# SCH_DS3231SupercapModule_2025-05-23.net
KiCad netlist of a schematic drawn in EasyEDA
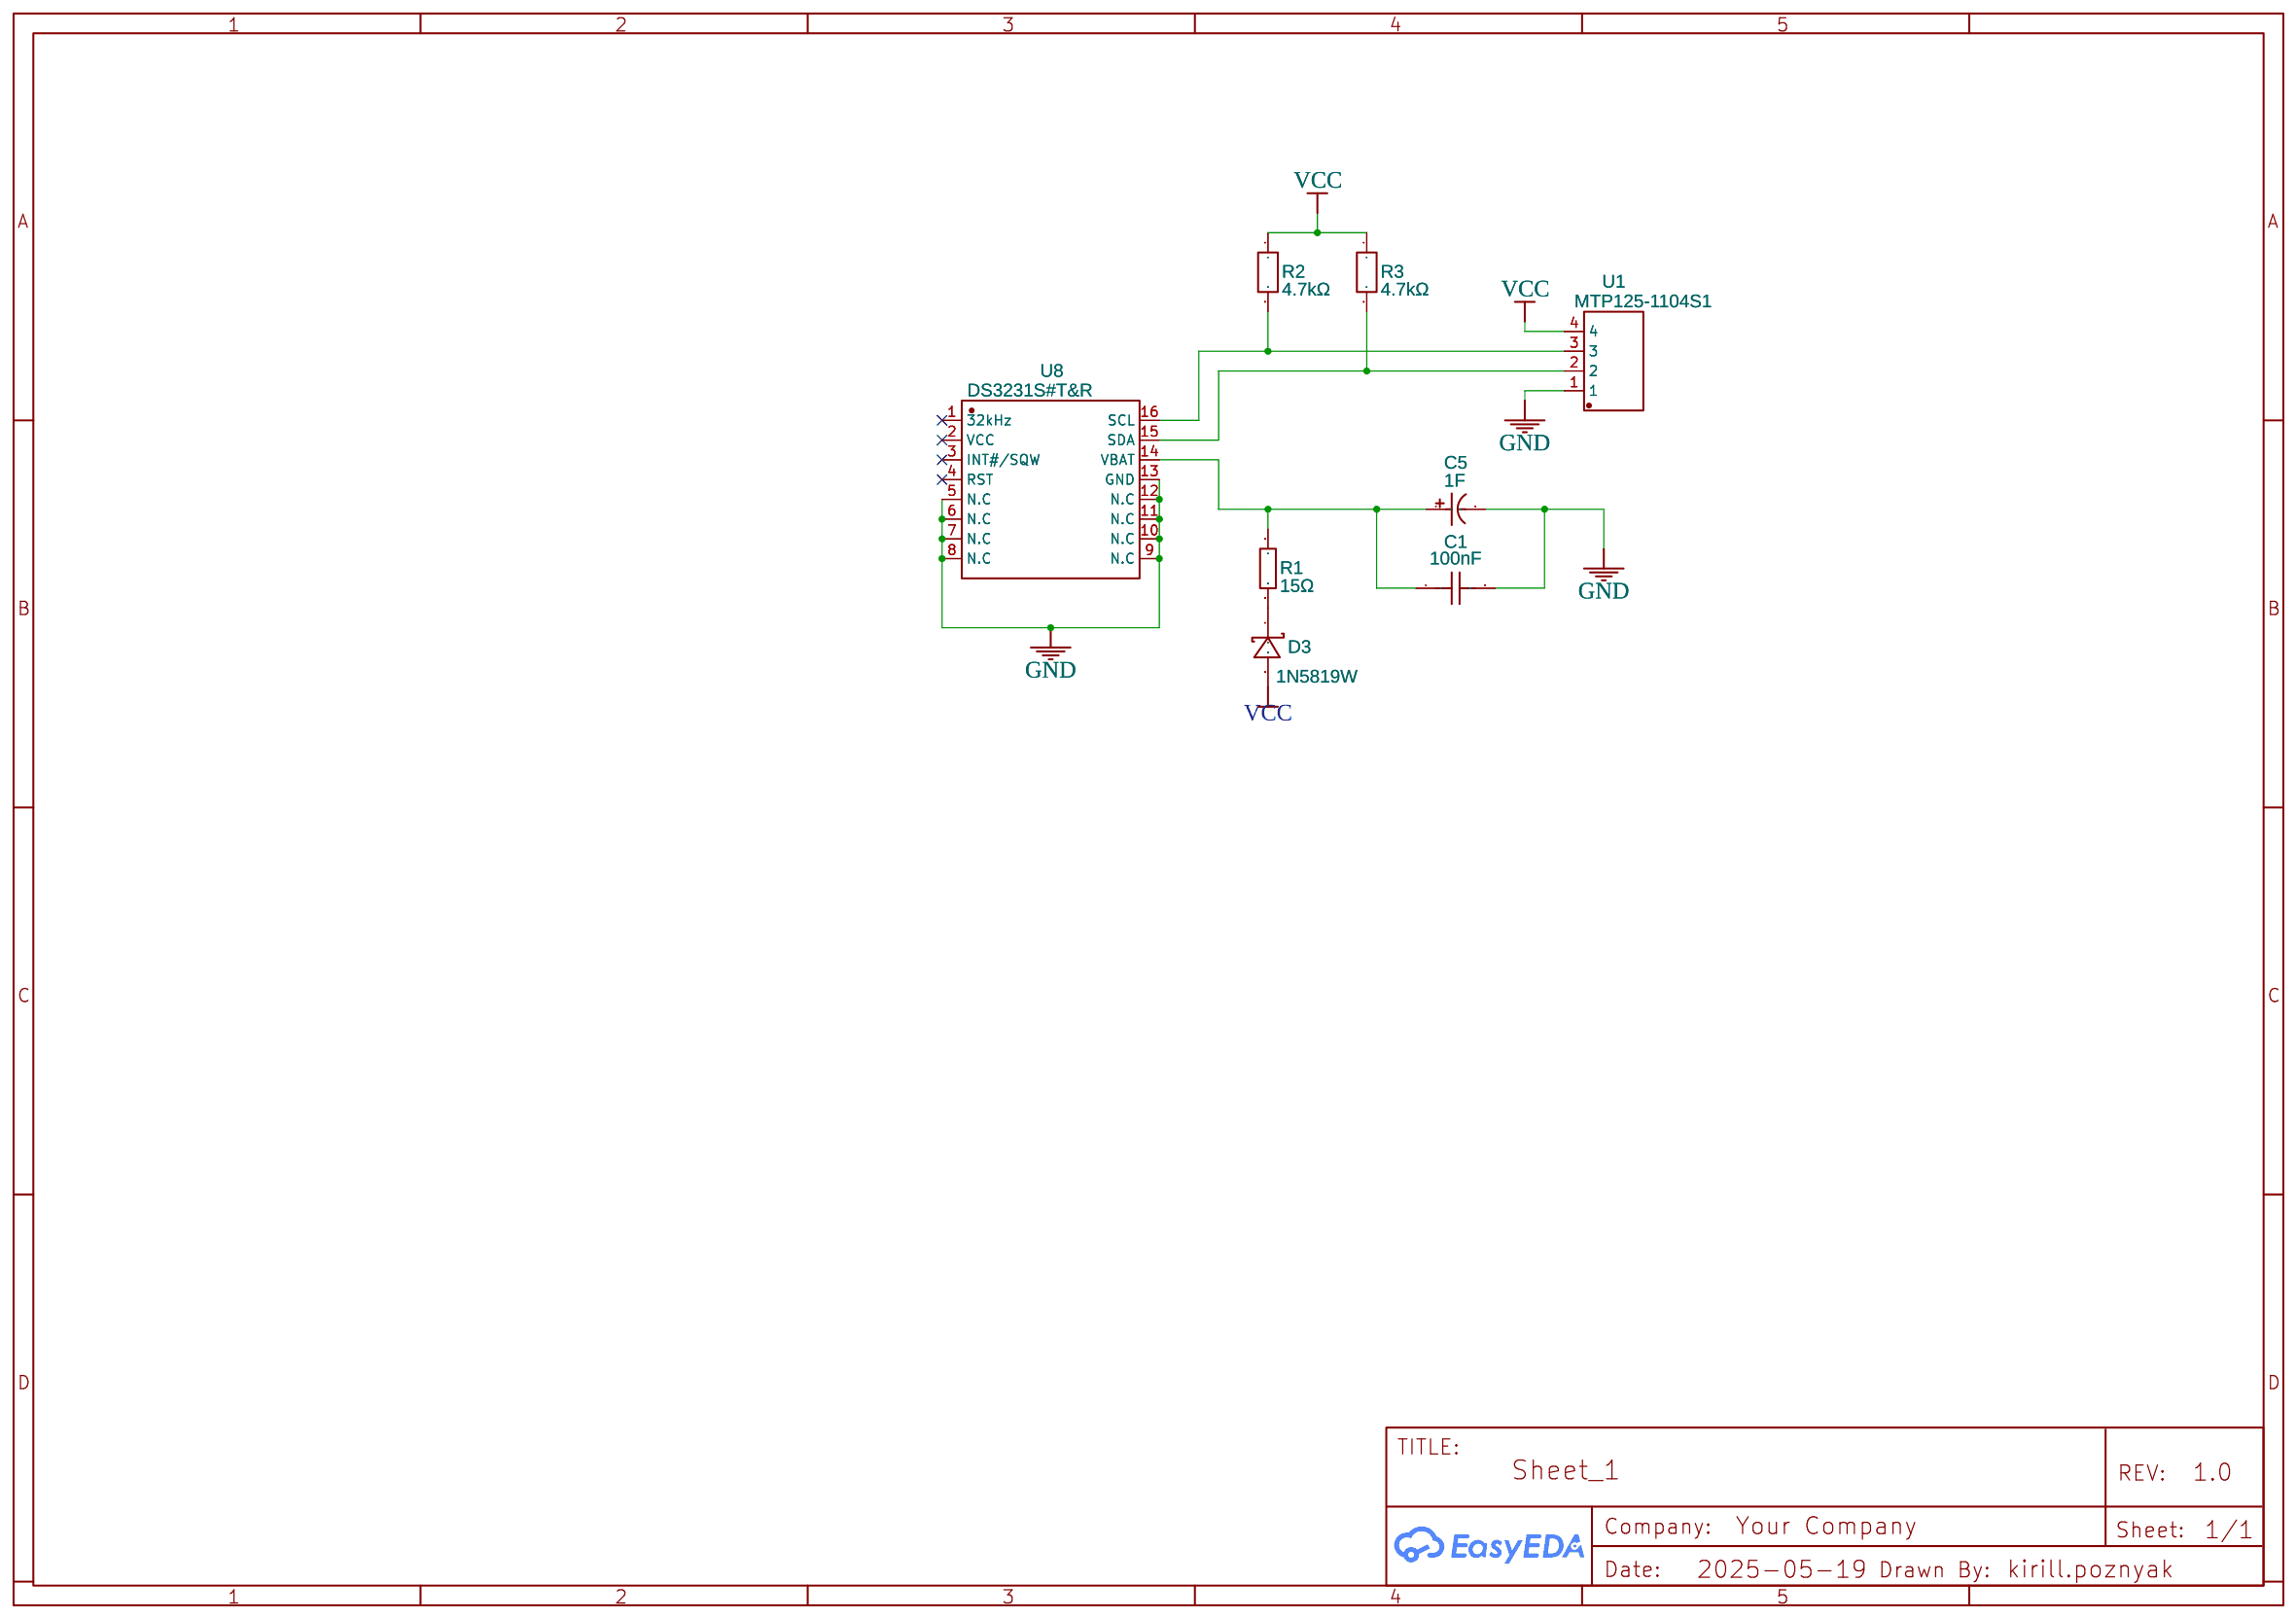
[diagram p0: schematic sheet]

(export (version "E")
  (design (tool "Eeschema 10.0.6"))
  (components
    (comp (ref "C1")
      (value "100nF")
      (fields (field (name "Manufacturer Part") "0805B104M500NT") (field (name "Manufacturer") "FH(风华)"))
      (libsource (lib "") (part "0805B104M500NT"))
    )
    (comp (ref "C5")
      (value "1F")
      (fields (field (name "Manufacturer Part") "DCL5R5105CF") (field (name "Manufacturer") "KORCHIP(高奇普)"))
      (libsource (lib "") (part "DCL5R5105CF"))
    )
    (comp (ref "D3")
      (value "1N5819W")
      (fields (field (name "Manufacturer") "晶导微电子"))
      (libsource (lib "") (part "1N5819W"))
    )
    (comp (ref "R1")
      (value "15Ω")
      (fields (field (name "Manufacturer Part") "CR0805J80150G") (field (name "Manufacturer") "LIZ(丽智电子)"))
      (libsource (lib "") (part "CR0805J80150G"))
    )
    (comp (ref "R2")
      (value "4.7kΩ")
      (fields (field (name "Manufacturer Part") "RT0805BRD074K7L") (field (name "Manufacturer") "YAGEO(国巨)"))
      (libsource (lib "") (part "RT0805BRD074K7L"))
    )
    (comp (ref "R3")
      (value "4.7kΩ")
      (fields (field (name "Manufacturer Part") "RT0805BRD074K7L") (field (name "Manufacturer") "YAGEO(国巨)"))
      (libsource (lib "") (part "RT0805BRD074K7L"))
    )
    (comp (ref "U1")
      (value "MTP125-1104S1")
      (fields (field (name "Manufacturer") "MINTRON(明硕)"))
      (libsource (lib "") (part "MTP125-1104S1"))
    )
    (comp (ref "U8")
      (value "DS3231S#T&R")
      (fields (field (name "Manufacturer") "ADI(亚德诺)/MAXIM(美信)"))
      (libsource (lib "") (part "DS3231S#T&amp;R"))
    )
  )
  (nets
    (net (code "1") (name "GND") (class "Default")
      (node (ref "C1") (pin "2") (pinfunction "2_2") (pintype "unspecified"))
      (node (ref "C5") (pin "2") (pinfunction "2_2") (pintype "input"))
      (node (ref "U1") (pin "1") (pinfunction "1_1") (pintype "unspecified"))
      (node (ref "U8") (pin "10") (pinfunction "N.C_10") (pintype "unspecified"))
      (node (ref "U8") (pin "11") (pinfunction "N.C_11") (pintype "unspecified"))
      (node (ref "U8") (pin "12") (pinfunction "N.C_12") (pintype "unspecified"))
      (node (ref "U8") (pin "13") (pinfunction "GND_13") (pintype "unspecified"))
      (node (ref "U8") (pin "5") (pinfunction "N.C_5") (pintype "unspecified"))
      (node (ref "U8") (pin "6") (pinfunction "N.C_6") (pintype "unspecified"))
      (node (ref "U8") (pin "7") (pinfunction "N.C_7") (pintype "unspecified"))
      (node (ref "U8") (pin "8") (pinfunction "N.C_8") (pintype "unspecified"))
      (node (ref "U8") (pin "9") (pinfunction "N.C_9") (pintype "unspecified"))
    )
    (net (code "2") (name "Net-(D3-Pad1)") (class "Default")
      (node (ref "D3") (pin "1") (pinfunction "1_1") (pintype "unspecified"))
      (node (ref "R1") (pin "2") (pinfunction "2_2") (pintype "input"))
    )
    (net (code "3") (name "Net-(U8-SCL)") (class "Default")
      (node (ref "R2") (pin "2") (pinfunction "2_2") (pintype "unspecified"))
      (node (ref "U1") (pin "3") (pinfunction "3_3") (pintype "unspecified"))
      (node (ref "U8") (pin "16") (pinfunction "SCL_16") (pintype "unspecified"))
    )
    (net (code "4") (name "Net-(U8-SDA)") (class "Default")
      (node (ref "R3") (pin "2") (pinfunction "2_2") (pintype "unspecified"))
      (node (ref "U1") (pin "2") (pinfunction "2_2") (pintype "unspecified"))
      (node (ref "U8") (pin "15") (pinfunction "SDA_15") (pintype "unspecified"))
    )
    (net (code "5") (name "Net-(U8-VBAT)") (class "Default")
      (node (ref "C1") (pin "1") (pinfunction "1_1") (pintype "unspecified"))
      (node (ref "C5") (pin "1") (pinfunction "1_1") (pintype "input"))
      (node (ref "R1") (pin "1") (pinfunction "1_1") (pintype "input"))
      (node (ref "U8") (pin "14") (pinfunction "VBAT_14") (pintype "unspecified"))
    )
    (net (code "6") (name "VCC") (class "Default")
      (node (ref "D3") (pin "2") (pinfunction "2_2") (pintype "unspecified"))
      (node (ref "R2") (pin "1") (pinfunction "1_1") (pintype "unspecified"))
      (node (ref "R3") (pin "1") (pinfunction "1_1") (pintype "unspecified"))
      (node (ref "U1") (pin "4") (pinfunction "4_4") (pintype "unspecified"))
    )
    (net (code "7") (name "unconnected-(U8-32kHz-Pad1)") (class "Default")
      (node (ref "U8") (pin "1") (pinfunction "32kHz_1") (pintype "unspecified+no_connect"))
    )
    (net (code "8") (name "unconnected-(U8-INT#{slash}SQW-Pad3)") (class "Default")
      (node (ref "U8") (pin "3") (pinfunction "INT#/SQW_3") (pintype "unspecified+no_connect"))
    )
    (net (code "9") (name "unconnected-(U8-RST-Pad4)") (class "Default")
      (node (ref "U8") (pin "4") (pinfunction "RST_4") (pintype "unspecified+no_connect"))
    )
    (net (code "10") (name "unconnected-(U8-VCC-Pad2)") (class "Default")
      (node (ref "U8") (pin "2") (pinfunction "VCC_2") (pintype "unspecified+no_connect"))
    )
  )
)
